# simongame01.net
KiCad netlist of a schematic drawn in EAGLE
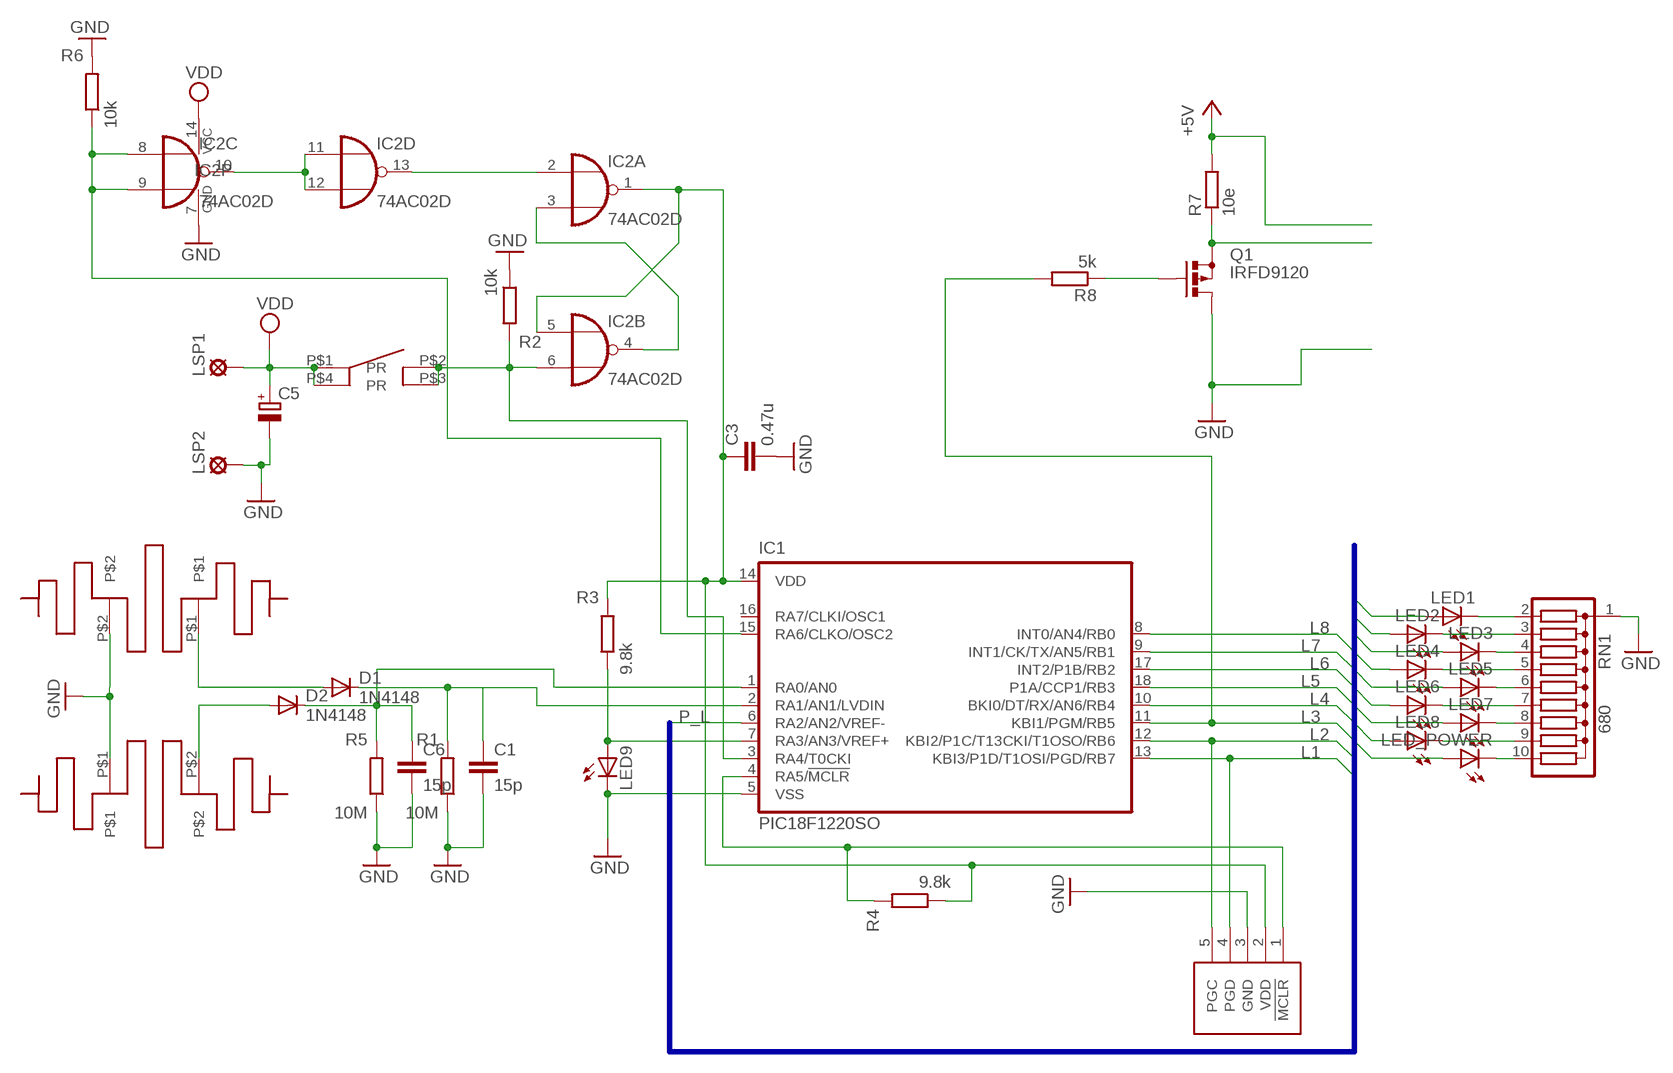
[diagram p0: schematic, sheet 1]

(export (version "E")
  (design (tool "Eeschema 10.0.6"))
  (components
    (comp (ref "C1")
      (value "15p")
      (footprint "eagle-import:C1206")
      (libsource (lib "eagle-import") (part "C-EUC1206"))
    )
    (comp (ref "C3")
      (value "0.47u")
      (footprint "eagle-import:C1206")
      (libsource (lib "eagle-import") (part "C-EUC1206"))
    )
    (comp (ref "C5")
      (value "CPOL-EUSMCA")
      (footprint "eagle-import:SMC_A")
      (libsource (lib "eagle-import") (part "CPOL-EUSMCA"))
    )
    (comp (ref "C6")
      (value "15p")
      (footprint "eagle-import:C1206")
      (libsource (lib "eagle-import") (part "C-EUC1206"))
    )
    (comp (ref "D1")
      (value "1N4148")
      (footprint "eagle-import:DO35-10")
      (libsource (lib "eagle-import") (part "1N4148"))
    )
    (comp (ref "D2")
      (value "1N4148")
      (footprint "eagle-import:DO35-10")
      (libsource (lib "eagle-import") (part "1N4148"))
    )
    (comp (ref "IC1")
      (value "PIC18F1220SO")
      (footprint "eagle-import:SO-18W")
      (libsource (lib "eagle-import") (part "PIC18F120SO2"))
    )
    (comp (ref "IC2")
      (value "74AC02D")
      (footprint "eagle-import:SO14")
      (libsource (lib "eagle-import") (part "7402DAC"))
    )
    (comp (ref "LED1")
      (value "LED3MM")
      (footprint "eagle-import:LED3MM")
      (libsource (lib "eagle-import") (part "LED3MM"))
    )
    (comp (ref "LED2")
      (value "LED3MM")
      (footprint "eagle-import:LED3MM")
      (libsource (lib "eagle-import") (part "LED3MM"))
    )
    (comp (ref "LED3")
      (value "LED3MM")
      (footprint "eagle-import:LED3MM")
      (libsource (lib "eagle-import") (part "LED3MM"))
    )
    (comp (ref "LED4")
      (value "LED3MM")
      (footprint "eagle-import:LED3MM")
      (libsource (lib "eagle-import") (part "LED3MM"))
    )
    (comp (ref "LED5")
      (value "LED3MM")
      (footprint "eagle-import:LED3MM")
      (libsource (lib "eagle-import") (part "LED3MM"))
    )
    (comp (ref "LED6")
      (value "LED3MM")
      (footprint "eagle-import:LED3MM")
      (libsource (lib "eagle-import") (part "LED3MM"))
    )
    (comp (ref "LED7")
      (value "LED3MM")
      (footprint "eagle-import:LED3MM")
      (libsource (lib "eagle-import") (part "LED3MM"))
    )
    (comp (ref "LED8")
      (value "LED3MM")
      (footprint "eagle-import:LED3MM")
      (libsource (lib "eagle-import") (part "LED3MM"))
    )
    (comp (ref "LED9")
      (value "LED5MM")
      (footprint "eagle-import:LED5MM")
      (libsource (lib "eagle-import") (part "LED5MM"))
    )
    (comp (ref "LED_POWER")
      (value "LED3MM")
      (footprint "eagle-import:LED3MM")
      (libsource (lib "eagle-import") (part "LED3MM"))
    )
    (comp (ref "LSP1")
      (value "SE14")
      (footprint "eagle-import:SE14")
      (libsource (lib "eagle-import") (part "SE14"))
    )
    (comp (ref "LSP2")
      (value "SE14")
      (footprint "eagle-import:SE14")
      (libsource (lib "eagle-import") (part "SE14"))
    )
    (comp (ref "Q1")
      (value "IRFD9120")
      (footprint "eagle-import:C370-01")
      (libsource (lib "eagle-import") (part "IRFD9120"))
    )
    (comp (ref "R1")
      (value "10M")
      (footprint "eagle-import:M1206")
      (libsource (lib "eagle-import") (part "R-EU_M1206"))
    )
    (comp (ref "R2")
      (value "10k")
      (footprint "eagle-import:M1206")
      (libsource (lib "eagle-import") (part "R-EU_M1206"))
    )
    (comp (ref "R3")
      (value "9.8k")
      (footprint "eagle-import:M1206")
      (libsource (lib "eagle-import") (part "R-EU_M1206"))
    )
    (comp (ref "R4")
      (value "9.8k")
      (footprint "eagle-import:M1206")
      (libsource (lib "eagle-import") (part "R-EU_M1206"))
    )
    (comp (ref "R5")
      (value "10M")
      (footprint "eagle-import:M1206")
      (libsource (lib "eagle-import") (part "R-EU_M1206"))
    )
    (comp (ref "R6")
      (value "10k")
      (footprint "eagle-import:M1206")
      (libsource (lib "eagle-import") (part "R-EU_M1206"))
    )
    (comp (ref "R7")
      (value "10e")
      (footprint "eagle-import:M1206")
      (libsource (lib "eagle-import") (part "R-EU_M1206"))
    )
    (comp (ref "R8")
      (value "5k")
      (footprint "eagle-import:M1206")
      (libsource (lib "eagle-import") (part "R-EU_M1206"))
    )
    (comp (ref "RN1")
      (value "680")
      (footprint "eagle-import:SIL10")
      (libsource (lib "eagle-import") (part "G09R"))
    )
    (comp (ref "U$1")
      (value "TIKBUTTON01")
      (footprint "eagle-import:TIKBUTTON01")
      (libsource (lib "eagle-import") (part "TIKBUTTON01"))
    )
    (comp (ref "U$2")
      (value "ANTENNA")
      (footprint "eagle-import:ANT!")
      (libsource (lib "eagle-import") (part "ANTENNA"))
    )
    (comp (ref "U$3")
      (value "ANTENNA")
      (footprint "eagle-import:ANT!")
      (libsource (lib "eagle-import") (part "ANTENNA"))
    )
    (comp (ref "U$4")
      (value "PIC-PROG-CON")
      (footprint "eagle-import:PIC-PROG-CON")
      (libsource (lib "eagle-import") (part "PIC-PROG-CON"))
    )
  )
  (nets
    (net (code "1") (name "+5V") (class "Default")
      (node (ref "R7") (pin "2") (pinfunction "2_2") (pintype "passive"))
    )
    (net (code "2") (name "/L1") (class "Default")
      (node (ref "IC1") (pin "13") (pinfunction "KBI3/P1D/T1OSI/PGD/RB7_13") (pintype "bidirectional"))
      (node (ref "LED1") (pin "A") (pinfunction "A_A") (pintype "passive"))
      (node (ref "U$4") (pin "4") (pinfunction "PGD_4") (pintype "bidirectional"))
    )
    (net (code "3") (name "/L2") (class "Default")
      (node (ref "IC1") (pin "12") (pinfunction "KBI2/P1C/T13CKI/T1OSO/RB6_12") (pintype "bidirectional"))
      (node (ref "LED2") (pin "A") (pinfunction "A_A") (pintype "passive"))
      (node (ref "U$4") (pin "5") (pinfunction "PGC_5") (pintype "bidirectional"))
    )
    (net (code "4") (name "/L3") (class "Default")
      (node (ref "IC1") (pin "11") (pinfunction "KBI1/PGM/RB5_11") (pintype "bidirectional"))
      (node (ref "LED3") (pin "A") (pinfunction "A_A") (pintype "passive"))
      (node (ref "R8") (pin "2") (pinfunction "2_2") (pintype "passive"))
    )
    (net (code "5") (name "/L4") (class "Default")
      (node (ref "IC1") (pin "10") (pinfunction "BKI0/DT/RX/AN6/RB4_10") (pintype "bidirectional"))
      (node (ref "LED4") (pin "A") (pinfunction "A_A") (pintype "passive"))
    )
    (net (code "6") (name "/L5") (class "Default")
      (node (ref "IC1") (pin "18") (pinfunction "P1A/CCP1/RB3_18") (pintype "bidirectional"))
      (node (ref "LED5") (pin "A") (pinfunction "A_A") (pintype "passive"))
    )
    (net (code "7") (name "/L6") (class "Default")
      (node (ref "IC1") (pin "17") (pinfunction "INT2/P1B/RB2_17") (pintype "bidirectional"))
      (node (ref "LED6") (pin "A") (pinfunction "A_A") (pintype "passive"))
    )
    (net (code "8") (name "/L7") (class "Default")
      (node (ref "IC1") (pin "9") (pinfunction "INT1/CK/TX/AN5/RB1_9") (pintype "bidirectional"))
      (node (ref "LED7") (pin "A") (pinfunction "A_A") (pintype "passive"))
    )
    (net (code "9") (name "/L8") (class "Default")
      (node (ref "IC1") (pin "8") (pinfunction "INT0/AN4/RB0_8") (pintype "bidirectional"))
      (node (ref "LED8") (pin "A") (pinfunction "A_A") (pintype "passive"))
    )
    (net (code "10") (name "/P_L") (class "Default")
      (node (ref "IC1") (pin "6") (pinfunction "RA2/AN2/VREF-_6") (pintype "bidirectional"))
      (node (ref "LED_POWER") (pin "A") (pinfunction "A_A") (pintype "passive"))
    )
    (net (code "11") (name "GND") (class "Default")
      (node (ref "C1") (pin "2") (pinfunction "2_2") (pintype "passive"))
      (node (ref "C3") (pin "2") (pinfunction "2_2") (pintype "passive"))
      (node (ref "C5") (pin "-") (pinfunction "-_-") (pintype "passive"))
      (node (ref "C6") (pin "2") (pinfunction "2_2") (pintype "passive"))
      (node (ref "IC1") (pin "5") (pinfunction "VSS_5") (pintype "power_in"))
      (node (ref "IC2") (pin "7") (pinfunction "GND_7") (pintype "power_in"))
      (node (ref "LED9") (pin "K") (pinfunction "C_K") (pintype "passive"))
      (node (ref "LSP2") (pin "MP") (pinfunction "MP_MP") (pintype "passive"))
      (node (ref "Q1") (pin "D1") (pinfunction "D1_D1") (pintype "passive"))
      (node (ref "R1") (pin "1") (pinfunction "1_1") (pintype "passive"))
      (node (ref "R2") (pin "1") (pinfunction "1_1") (pintype "passive"))
      (node (ref "R5") (pin "1") (pinfunction "1_1") (pintype "passive"))
      (node (ref "R6") (pin "2") (pinfunction "2_2") (pintype "passive"))
      (node (ref "RN1") (pin "1") (pinfunction "1_1") (pintype "passive"))
      (node (ref "U$2") (pin "P$1") (pinfunction "P$1_P$1") (pintype "bidirectional"))
      (node (ref "U$3") (pin "P$2") (pinfunction "P$2_P$2") (pintype "bidirectional"))
      (node (ref "U$4") (pin "3") (pinfunction "GND_3") (pintype "bidirectional"))
    )
    (net (code "12") (name "Net-(D1-PadA)") (class "Default")
      (node (ref "D1") (pin "A") (pinfunction "A_A") (pintype "passive"))
      (node (ref "U$3") (pin "P$1") (pinfunction "P$1_P$1") (pintype "bidirectional"))
    )
    (net (code "13") (name "Net-(D2-PadA)") (class "Default")
      (node (ref "D2") (pin "A") (pinfunction "A_A") (pintype "passive"))
      (node (ref "U$2") (pin "P$2") (pinfunction "P$2_P$2") (pintype "bidirectional"))
    )
    (net (code "14") (name "Net-(IC1-RA0{slash}AN0)") (class "Default")
      (node (ref "C6") (pin "1") (pinfunction "1_1") (pintype "passive"))
      (node (ref "D2") (pin "C") (pinfunction "C_C") (pintype "passive"))
      (node (ref "IC1") (pin "1") (pinfunction "RA0/AN0_1") (pintype "bidirectional"))
      (node (ref "R5") (pin "2") (pinfunction "2_2") (pintype "passive"))
    )
    (net (code "15") (name "Net-(IC1-RA1{slash}AN1{slash}LVDIN)") (class "Default")
      (node (ref "C1") (pin "1") (pinfunction "1_1") (pintype "passive"))
      (node (ref "D1") (pin "C") (pinfunction "C_C") (pintype "passive"))
      (node (ref "IC1") (pin "2") (pinfunction "RA1/AN1/LVDIN_2") (pintype "bidirectional"))
      (node (ref "R1") (pin "2") (pinfunction "2_2") (pintype "passive"))
    )
    (net (code "16") (name "Net-(IC1-RA3{slash}AN3{slash}VREF+)") (class "Default")
      (node (ref "IC1") (pin "7") (pinfunction "RA3/AN3/VREF+_7") (pintype "bidirectional"))
      (node (ref "LED9") (pin "A") (pinfunction "A_A") (pintype "passive"))
      (node (ref "R3") (pin "1") (pinfunction "1_1") (pintype "passive"))
    )
    (net (code "17") (name "Net-(IC1-RA4{slash}T0CKI)") (class "Default")
      (node (ref "IC1") (pin "3") (pinfunction "RA4/T0CKI_3") (pintype "bidirectional"))
      (node (ref "IC2") (pin "6") (pinfunction "I1_6") (pintype "input"))
      (node (ref "R2") (pin "2") (pinfunction "2_2") (pintype "passive"))
      (node (ref "U$1") (pin "P$2") (pinfunction "R_P$2") (pintype "output"))
      (node (ref "U$1") (pin "P$3") (pinfunction "R_P$3") (pintype "bidirectional"))
    )
    (net (code "18") (name "Net-(IC1-RA5{slash}~{MCLR})") (class "Default")
      (node (ref "IC1") (pin "4") (pinfunction "RA5/~{MCLR}_4") (pintype "input"))
      (node (ref "R4") (pin "2") (pinfunction "2_2") (pintype "passive"))
      (node (ref "U$4") (pin "1") (pinfunction "~{MCLR}_1") (pintype "bidirectional"))
    )
    (net (code "19") (name "Net-(IC1-RA6{slash}CLKO{slash}OSC2)") (class "Default")
      (node (ref "IC1") (pin "15") (pinfunction "RA6/CLKO/OSC2_15") (pintype "bidirectional"))
      (node (ref "IC2") (pin "8") (pinfunction "I0_8") (pintype "input"))
      (node (ref "IC2") (pin "9") (pinfunction "I1_9") (pintype "input"))
      (node (ref "R6") (pin "1") (pinfunction "1_1") (pintype "passive"))
    )
    (net (code "20") (name "Net-(IC1-VDD)") (class "Default")
      (node (ref "C3") (pin "1") (pinfunction "1_1") (pintype "passive"))
      (node (ref "IC1") (pin "14") (pinfunction "VDD_14") (pintype "power_in"))
      (node (ref "IC2") (pin "1") (pinfunction "O_1") (pintype "output"))
      (node (ref "IC2") (pin "5") (pinfunction "I0_5") (pintype "input"))
      (node (ref "R3") (pin "2") (pinfunction "2_2") (pintype "passive"))
      (node (ref "R4") (pin "1") (pinfunction "1_1") (pintype "passive"))
      (node (ref "U$4") (pin "2") (pinfunction "VDD_2") (pintype "bidirectional"))
    )
    (net (code "21") (name "Net-(IC2A-I0)") (class "Default")
      (node (ref "IC2") (pin "13") (pinfunction "O_13") (pintype "output"))
      (node (ref "IC2") (pin "2") (pinfunction "I0_2") (pintype "input"))
    )
    (net (code "22") (name "Net-(IC2A-I1)") (class "Default")
      (node (ref "IC2") (pin "3") (pinfunction "I1_3") (pintype "input"))
      (node (ref "IC2") (pin "4") (pinfunction "O_4") (pintype "output"))
    )
    (net (code "23") (name "Net-(IC2C-O)") (class "Default")
      (node (ref "IC2") (pin "10") (pinfunction "O_10") (pintype "output"))
      (node (ref "IC2") (pin "11") (pinfunction "I0_11") (pintype "input"))
      (node (ref "IC2") (pin "12") (pinfunction "I1_12") (pintype "input"))
    )
    (net (code "24") (name "Net-(LED1-C)") (class "Default")
      (node (ref "LED1") (pin "K") (pinfunction "C_K") (pintype "passive"))
      (node (ref "RN1") (pin "2") (pinfunction "2_2") (pintype "passive"))
    )
    (net (code "25") (name "Net-(LED2-C)") (class "Default")
      (node (ref "LED2") (pin "K") (pinfunction "C_K") (pintype "passive"))
      (node (ref "RN1") (pin "3") (pinfunction "3_3") (pintype "passive"))
    )
    (net (code "26") (name "Net-(LED3-C)") (class "Default")
      (node (ref "LED3") (pin "K") (pinfunction "C_K") (pintype "passive"))
      (node (ref "RN1") (pin "4") (pinfunction "4_4") (pintype "passive"))
    )
    (net (code "27") (name "Net-(LED4-C)") (class "Default")
      (node (ref "LED4") (pin "K") (pinfunction "C_K") (pintype "passive"))
      (node (ref "RN1") (pin "5") (pinfunction "5_5") (pintype "passive"))
    )
    (net (code "28") (name "Net-(LED5-C)") (class "Default")
      (node (ref "LED5") (pin "K") (pinfunction "C_K") (pintype "passive"))
      (node (ref "RN1") (pin "6") (pinfunction "6_6") (pintype "passive"))
    )
    (net (code "29") (name "Net-(LED6-C)") (class "Default")
      (node (ref "LED6") (pin "K") (pinfunction "C_K") (pintype "passive"))
      (node (ref "RN1") (pin "7") (pinfunction "7_7") (pintype "passive"))
    )
    (net (code "30") (name "Net-(LED7-C)") (class "Default")
      (node (ref "LED7") (pin "K") (pinfunction "C_K") (pintype "passive"))
      (node (ref "RN1") (pin "8") (pinfunction "8_8") (pintype "passive"))
    )
    (net (code "31") (name "Net-(LED8-C)") (class "Default")
      (node (ref "LED8") (pin "K") (pinfunction "C_K") (pintype "passive"))
      (node (ref "RN1") (pin "9") (pinfunction "9_9") (pintype "passive"))
    )
    (net (code "32") (name "Net-(LED_POWER-C)") (class "Default")
      (node (ref "LED_POWER") (pin "K") (pinfunction "C_K") (pintype "passive"))
      (node (ref "RN1") (pin "10") (pinfunction "10_10") (pintype "passive"))
    )
    (net (code "33") (name "Net-(Q1-PadG)") (class "Default")
      (node (ref "Q1") (pin "G") (pinfunction "G_G") (pintype "passive"))
      (node (ref "R8") (pin "1") (pinfunction "1_1") (pintype "passive"))
    )
    (net (code "34") (name "Net-(Q1-PadS)") (class "Default")
      (node (ref "Q1") (pin "S") (pinfunction "S_S") (pintype "passive"))
      (node (ref "R7") (pin "1") (pinfunction "1_1") (pintype "passive"))
    )
    (net (code "35") (name "VDD") (class "Default")
      (node (ref "C5") (pin "+") (pinfunction "+_+") (pintype "passive"))
      (node (ref "IC2") (pin "14") (pinfunction "VCC_14") (pintype "power_in"))
      (node (ref "LSP1") (pin "MP") (pinfunction "MP_MP") (pintype "passive"))
      (node (ref "U$1") (pin "P$1") (pinfunction "P_P$1") (pintype "input"))
      (node (ref "U$1") (pin "P$4") (pinfunction "P_P$4") (pintype "bidirectional"))
    )
    (net (code "36") (name "unconnected-(IC1-RA7{slash}CLKI{slash}OSC1-Pad16)") (class "Default")
      (node (ref "IC1") (pin "16") (pinfunction "RA7/CLKI/OSC1_16") (pintype "bidirectional"))
    )
    (net (code "37") (name "unconnected-(Q1-PadD)") (class "Default")
      (node (ref "Q1") (pin "D") (pinfunction "D_D") (pintype "passive"))
    )
  )
)
